# FAL65816_ram.net
KiCad netlist of a schematic drawn in EAGLE
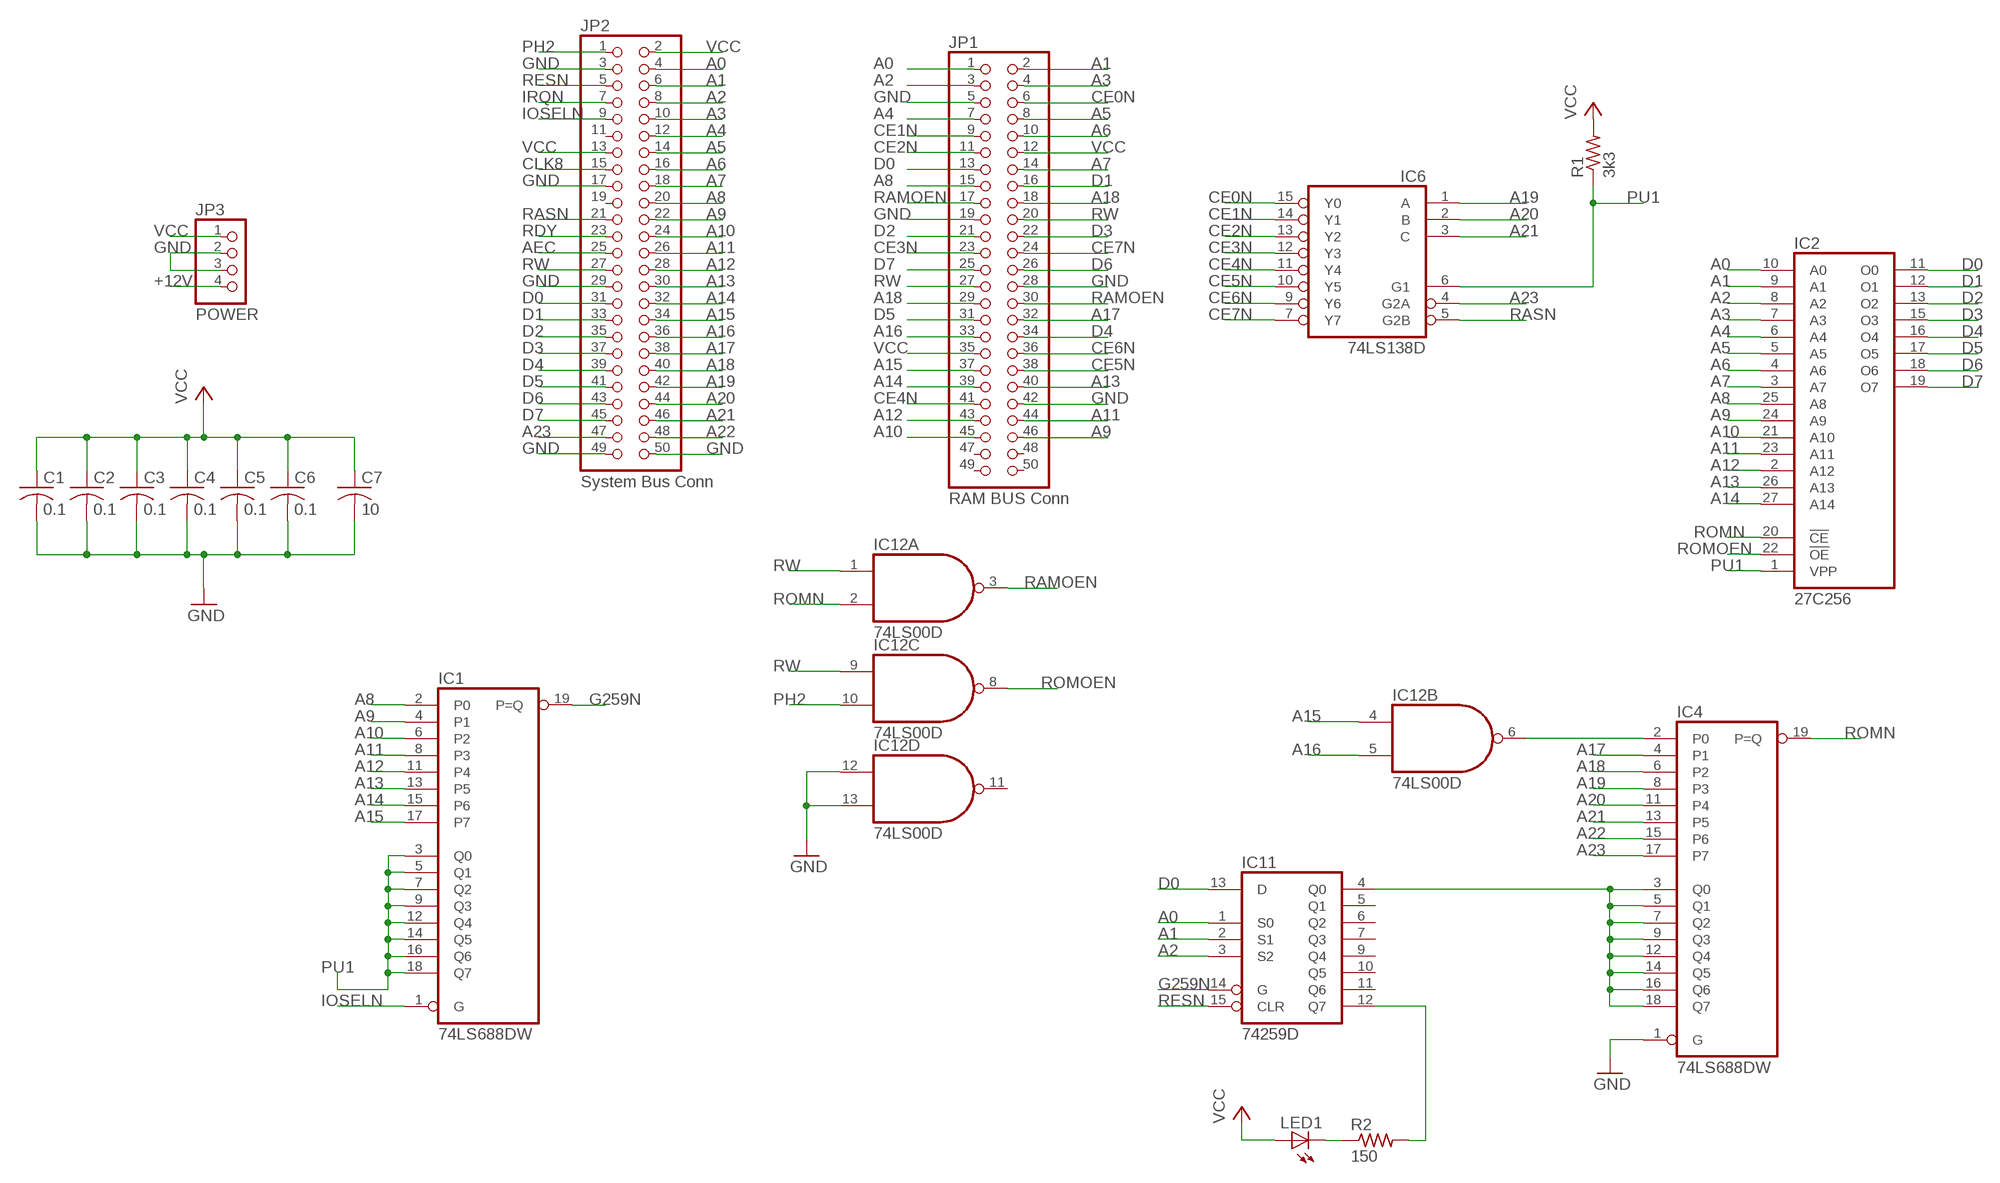
[diagram p0: schematic, sheet 1]

(export (version "E")
  (design (tool "Eeschema 10.0.6"))
  (components
    (comp (ref "C1")
      (value "0.1")
      (footprint "eagle-import:C050-024X044")
      (libsource (lib "eagle-import") (part "C-US050-024X044"))
    )
    (comp (ref "C2")
      (value "0.1")
      (footprint "eagle-import:C050-024X044")
      (libsource (lib "eagle-import") (part "C-US050-024X044"))
    )
    (comp (ref "C3")
      (value "0.1")
      (footprint "eagle-import:C050-024X044")
      (libsource (lib "eagle-import") (part "C-US050-024X044"))
    )
    (comp (ref "C4")
      (value "0.1")
      (footprint "eagle-import:C050-024X044")
      (libsource (lib "eagle-import") (part "C-US050-024X044"))
    )
    (comp (ref "C5")
      (value "0.1")
      (footprint "eagle-import:C050-024X044")
      (libsource (lib "eagle-import") (part "C-US050-024X044"))
    )
    (comp (ref "C6")
      (value "0.1")
      (footprint "eagle-import:C050-024X044")
      (libsource (lib "eagle-import") (part "C-US050-024X044"))
    )
    (comp (ref "C7")
      (value "10")
      (footprint "eagle-import:C050-024X044")
      (libsource (lib "eagle-import") (part "C-US050-024X044"))
    )
    (comp (ref "IC1")
      (value "74LS688DW")
      (footprint "eagle-import:SO20W")
      (libsource (lib "eagle-import") (part "74688DWLS"))
    )
    (comp (ref "IC2")
      (value "27C256")
      (footprint "eagle-import:DIL28")
      (libsource (lib "eagle-import") (part "27256"))
    )
    (comp (ref "IC4")
      (value "74LS688DW")
      (footprint "eagle-import:SO20W")
      (libsource (lib "eagle-import") (part "74688DWLS"))
    )
    (comp (ref "IC6")
      (value "74LS138D")
      (footprint "eagle-import:SO16")
      (libsource (lib "eagle-import") (part "74138DLS"))
    )
    (comp (ref "IC11")
      (value "74259D")
      (footprint "eagle-import:SO16")
      (libsource (lib "eagle-import") (part "74259D"))
    )
    (comp (ref "IC12")
      (value "74LS00D")
      (footprint "eagle-import:SO14")
      (libsource (lib "eagle-import") (part "7400DLS"))
    )
    (comp (ref "JP1")
      (value "RAM BUS Conn")
      (footprint "eagle-import:2X25_90")
      (libsource (lib "eagle-import") (part "PINHD-2X25/90"))
    )
    (comp (ref "JP2")
      (value "System Bus Conn")
      (footprint "eagle-import:2X25_90")
      (libsource (lib "eagle-import") (part "PINHD-2X25/90"))
    )
    (comp (ref "JP3")
      (value "POWER")
      (footprint "eagle-import:1X04_90")
      (libsource (lib "eagle-import") (part "PINHD-1X4/90"))
    )
    (comp (ref "LED1")
      (value "LED5MM")
      (footprint "eagle-import:LED5MM")
      (libsource (lib "eagle-import") (part "LED5MM"))
    )
    (comp (ref "R1")
      (value "3k3")
      (footprint "eagle-import:0204_7")
      (libsource (lib "eagle-import") (part "R-US_0204/7"))
    )
    (comp (ref "R2")
      (value "150")
      (footprint "eagle-import:0204_7")
      (libsource (lib "eagle-import") (part "R-US_0204/7"))
    )
  )
  (nets
    (net (code "1") (name "/+12V") (class "Default")
      (node (ref "JP3") (pin "4") (pinfunction "4_4") (pintype "passive"))
    )
    (net (code "2") (name "/A0") (class "Default")
      (node (ref "IC11") (pin "1") (pinfunction "S0_1") (pintype "input"))
      (node (ref "IC2") (pin "10") (pinfunction "A0_10") (pintype "input"))
      (node (ref "JP1") (pin "1") (pinfunction "1_1") (pintype "passive"))
      (node (ref "JP2") (pin "4") (pinfunction "4_4") (pintype "passive"))
    )
    (net (code "3") (name "/A1") (class "Default")
      (node (ref "IC11") (pin "2") (pinfunction "S1_2") (pintype "input"))
      (node (ref "IC2") (pin "9") (pinfunction "A1_9") (pintype "input"))
      (node (ref "JP1") (pin "2") (pinfunction "2_2") (pintype "passive"))
      (node (ref "JP2") (pin "6") (pinfunction "6_6") (pintype "passive"))
    )
    (net (code "4") (name "/A2") (class "Default")
      (node (ref "IC11") (pin "3") (pinfunction "S2_3") (pintype "input"))
      (node (ref "IC2") (pin "8") (pinfunction "A2_8") (pintype "input"))
      (node (ref "JP1") (pin "3") (pinfunction "3_3") (pintype "passive"))
      (node (ref "JP2") (pin "8") (pinfunction "8_8") (pintype "passive"))
    )
    (net (code "5") (name "/A3") (class "Default")
      (node (ref "IC2") (pin "7") (pinfunction "A3_7") (pintype "input"))
      (node (ref "JP1") (pin "4") (pinfunction "4_4") (pintype "passive"))
      (node (ref "JP2") (pin "10") (pinfunction "10_10") (pintype "passive"))
    )
    (net (code "6") (name "/A4") (class "Default")
      (node (ref "IC2") (pin "6") (pinfunction "A4_6") (pintype "input"))
      (node (ref "JP1") (pin "7") (pinfunction "7_7") (pintype "passive"))
      (node (ref "JP2") (pin "12") (pinfunction "12_12") (pintype "passive"))
    )
    (net (code "7") (name "/A5") (class "Default")
      (node (ref "IC2") (pin "5") (pinfunction "A5_5") (pintype "input"))
      (node (ref "JP1") (pin "8") (pinfunction "8_8") (pintype "passive"))
      (node (ref "JP2") (pin "14") (pinfunction "14_14") (pintype "passive"))
    )
    (net (code "8") (name "/A6") (class "Default")
      (node (ref "IC2") (pin "4") (pinfunction "A6_4") (pintype "input"))
      (node (ref "JP1") (pin "10") (pinfunction "10_10") (pintype "passive"))
      (node (ref "JP2") (pin "16") (pinfunction "16_16") (pintype "passive"))
    )
    (net (code "9") (name "/A7") (class "Default")
      (node (ref "IC2") (pin "3") (pinfunction "A7_3") (pintype "input"))
      (node (ref "JP1") (pin "14") (pinfunction "14_14") (pintype "passive"))
      (node (ref "JP2") (pin "18") (pinfunction "18_18") (pintype "passive"))
    )
    (net (code "10") (name "/A8") (class "Default")
      (node (ref "IC1") (pin "2") (pinfunction "P0_2") (pintype "input"))
      (node (ref "IC2") (pin "25") (pinfunction "A8_25") (pintype "input"))
      (node (ref "JP1") (pin "15") (pinfunction "15_15") (pintype "passive"))
      (node (ref "JP2") (pin "20") (pinfunction "20_20") (pintype "passive"))
    )
    (net (code "11") (name "/A9") (class "Default")
      (node (ref "IC1") (pin "4") (pinfunction "P1_4") (pintype "input"))
      (node (ref "IC2") (pin "24") (pinfunction "A9_24") (pintype "input"))
      (node (ref "JP1") (pin "46") (pinfunction "46_46") (pintype "passive"))
      (node (ref "JP2") (pin "22") (pinfunction "22_22") (pintype "passive"))
    )
    (net (code "12") (name "/A10") (class "Default")
      (node (ref "IC1") (pin "6") (pinfunction "P2_6") (pintype "input"))
      (node (ref "IC2") (pin "21") (pinfunction "A10_21") (pintype "input"))
      (node (ref "JP1") (pin "45") (pinfunction "45_45") (pintype "passive"))
      (node (ref "JP2") (pin "24") (pinfunction "24_24") (pintype "passive"))
    )
    (net (code "13") (name "/A11") (class "Default")
      (node (ref "IC1") (pin "8") (pinfunction "P3_8") (pintype "input"))
      (node (ref "IC2") (pin "23") (pinfunction "A11_23") (pintype "input"))
      (node (ref "JP1") (pin "44") (pinfunction "44_44") (pintype "passive"))
      (node (ref "JP2") (pin "26") (pinfunction "26_26") (pintype "passive"))
    )
    (net (code "14") (name "/A12") (class "Default")
      (node (ref "IC1") (pin "11") (pinfunction "P4_11") (pintype "input"))
      (node (ref "IC2") (pin "2") (pinfunction "A12_2") (pintype "input"))
      (node (ref "JP1") (pin "43") (pinfunction "43_43") (pintype "passive"))
      (node (ref "JP2") (pin "28") (pinfunction "28_28") (pintype "passive"))
    )
    (net (code "15") (name "/A13") (class "Default")
      (node (ref "IC1") (pin "13") (pinfunction "P5_13") (pintype "input"))
      (node (ref "IC2") (pin "26") (pinfunction "A13_26") (pintype "input"))
      (node (ref "JP1") (pin "40") (pinfunction "40_40") (pintype "passive"))
      (node (ref "JP2") (pin "30") (pinfunction "30_30") (pintype "passive"))
    )
    (net (code "16") (name "/A14") (class "Default")
      (node (ref "IC1") (pin "15") (pinfunction "P6_15") (pintype "input"))
      (node (ref "IC2") (pin "27") (pinfunction "A14_27") (pintype "input"))
      (node (ref "JP1") (pin "39") (pinfunction "39_39") (pintype "passive"))
      (node (ref "JP2") (pin "32") (pinfunction "32_32") (pintype "passive"))
    )
    (net (code "17") (name "/A15") (class "Default")
      (node (ref "IC1") (pin "17") (pinfunction "P7_17") (pintype "input"))
      (node (ref "IC12") (pin "4") (pinfunction "I0_4") (pintype "input"))
      (node (ref "JP1") (pin "37") (pinfunction "37_37") (pintype "passive"))
      (node (ref "JP2") (pin "34") (pinfunction "34_34") (pintype "passive"))
    )
    (net (code "18") (name "/A16") (class "Default")
      (node (ref "IC12") (pin "5") (pinfunction "I1_5") (pintype "input"))
      (node (ref "JP1") (pin "33") (pinfunction "33_33") (pintype "passive"))
      (node (ref "JP2") (pin "36") (pinfunction "36_36") (pintype "passive"))
    )
    (net (code "19") (name "/A17") (class "Default")
      (node (ref "IC4") (pin "4") (pinfunction "P1_4") (pintype "input"))
      (node (ref "JP1") (pin "32") (pinfunction "32_32") (pintype "passive"))
      (node (ref "JP2") (pin "38") (pinfunction "38_38") (pintype "passive"))
    )
    (net (code "20") (name "/A18") (class "Default")
      (node (ref "IC4") (pin "6") (pinfunction "P2_6") (pintype "input"))
      (node (ref "JP1") (pin "18") (pinfunction "18_18") (pintype "passive"))
      (node (ref "JP1") (pin "29") (pinfunction "29_29") (pintype "passive"))
      (node (ref "JP2") (pin "40") (pinfunction "40_40") (pintype "passive"))
    )
    (net (code "21") (name "/A19") (class "Default")
      (node (ref "IC4") (pin "8") (pinfunction "P3_8") (pintype "input"))
      (node (ref "IC6") (pin "1") (pinfunction "A_1") (pintype "input"))
      (node (ref "JP2") (pin "42") (pinfunction "42_42") (pintype "passive"))
    )
    (net (code "22") (name "/A20") (class "Default")
      (node (ref "IC4") (pin "11") (pinfunction "P4_11") (pintype "input"))
      (node (ref "IC6") (pin "2") (pinfunction "B_2") (pintype "input"))
      (node (ref "JP2") (pin "44") (pinfunction "44_44") (pintype "passive"))
    )
    (net (code "23") (name "/A21") (class "Default")
      (node (ref "IC4") (pin "13") (pinfunction "P5_13") (pintype "input"))
      (node (ref "IC6") (pin "3") (pinfunction "C_3") (pintype "input"))
      (node (ref "JP2") (pin "46") (pinfunction "46_46") (pintype "passive"))
    )
    (net (code "24") (name "/A22") (class "Default")
      (node (ref "IC4") (pin "15") (pinfunction "P6_15") (pintype "input"))
      (node (ref "JP2") (pin "48") (pinfunction "48_48") (pintype "passive"))
    )
    (net (code "25") (name "/A23") (class "Default")
      (node (ref "IC4") (pin "17") (pinfunction "P7_17") (pintype "input"))
      (node (ref "IC6") (pin "4") (pinfunction "G2A_4") (pintype "input"))
      (node (ref "JP2") (pin "47") (pinfunction "47_47") (pintype "passive"))
    )
    (net (code "26") (name "/AEC") (class "Default")
      (node (ref "JP2") (pin "25") (pinfunction "25_25") (pintype "passive"))
    )
    (net (code "27") (name "/CE0N") (class "Default")
      (node (ref "IC6") (pin "15") (pinfunction "Y0_15") (pintype "output"))
      (node (ref "JP1") (pin "6") (pinfunction "6_6") (pintype "passive"))
    )
    (net (code "28") (name "/CE1N") (class "Default")
      (node (ref "IC6") (pin "14") (pinfunction "Y1_14") (pintype "output"))
      (node (ref "JP1") (pin "9") (pinfunction "9_9") (pintype "passive"))
    )
    (net (code "29") (name "/CE2N") (class "Default")
      (node (ref "IC6") (pin "13") (pinfunction "Y2_13") (pintype "output"))
      (node (ref "JP1") (pin "11") (pinfunction "11_11") (pintype "passive"))
    )
    (net (code "30") (name "/CE3N") (class "Default")
      (node (ref "IC6") (pin "12") (pinfunction "Y3_12") (pintype "output"))
      (node (ref "JP1") (pin "23") (pinfunction "23_23") (pintype "passive"))
    )
    (net (code "31") (name "/CE4N") (class "Default")
      (node (ref "IC6") (pin "11") (pinfunction "Y4_11") (pintype "output"))
      (node (ref "JP1") (pin "41") (pinfunction "41_41") (pintype "passive"))
    )
    (net (code "32") (name "/CE5N") (class "Default")
      (node (ref "IC6") (pin "10") (pinfunction "Y5_10") (pintype "output"))
      (node (ref "JP1") (pin "38") (pinfunction "38_38") (pintype "passive"))
    )
    (net (code "33") (name "/CE6N") (class "Default")
      (node (ref "IC6") (pin "9") (pinfunction "Y6_9") (pintype "output"))
      (node (ref "JP1") (pin "36") (pinfunction "36_36") (pintype "passive"))
    )
    (net (code "34") (name "/CE7N") (class "Default")
      (node (ref "IC6") (pin "7") (pinfunction "Y7_7") (pintype "output"))
      (node (ref "JP1") (pin "24") (pinfunction "24_24") (pintype "passive"))
    )
    (net (code "35") (name "/CLK8") (class "Default")
      (node (ref "JP2") (pin "15") (pinfunction "15_15") (pintype "passive"))
    )
    (net (code "36") (name "/D0") (class "Default")
      (node (ref "IC11") (pin "13") (pinfunction "D_13") (pintype "input"))
      (node (ref "IC2") (pin "11") (pinfunction "O0_11") (pintype "tri_state"))
      (node (ref "JP1") (pin "13") (pinfunction "13_13") (pintype "passive"))
      (node (ref "JP2") (pin "31") (pinfunction "31_31") (pintype "passive"))
    )
    (net (code "37") (name "/D1") (class "Default")
      (node (ref "IC2") (pin "12") (pinfunction "O1_12") (pintype "tri_state"))
      (node (ref "JP1") (pin "16") (pinfunction "16_16") (pintype "passive"))
      (node (ref "JP2") (pin "33") (pinfunction "33_33") (pintype "passive"))
    )
    (net (code "38") (name "/D2") (class "Default")
      (node (ref "IC2") (pin "13") (pinfunction "O2_13") (pintype "tri_state"))
      (node (ref "JP1") (pin "21") (pinfunction "21_21") (pintype "passive"))
      (node (ref "JP2") (pin "35") (pinfunction "35_35") (pintype "passive"))
    )
    (net (code "39") (name "/D3") (class "Default")
      (node (ref "IC2") (pin "15") (pinfunction "O3_15") (pintype "tri_state"))
      (node (ref "JP1") (pin "22") (pinfunction "22_22") (pintype "passive"))
      (node (ref "JP2") (pin "37") (pinfunction "37_37") (pintype "passive"))
    )
    (net (code "40") (name "/D4") (class "Default")
      (node (ref "IC2") (pin "16") (pinfunction "O4_16") (pintype "tri_state"))
      (node (ref "JP1") (pin "34") (pinfunction "34_34") (pintype "passive"))
      (node (ref "JP2") (pin "39") (pinfunction "39_39") (pintype "passive"))
    )
    (net (code "41") (name "/D5") (class "Default")
      (node (ref "IC2") (pin "17") (pinfunction "O5_17") (pintype "tri_state"))
      (node (ref "JP1") (pin "31") (pinfunction "31_31") (pintype "passive"))
      (node (ref "JP2") (pin "41") (pinfunction "41_41") (pintype "passive"))
    )
    (net (code "42") (name "/D6") (class "Default")
      (node (ref "IC2") (pin "18") (pinfunction "O6_18") (pintype "tri_state"))
      (node (ref "JP1") (pin "26") (pinfunction "26_26") (pintype "passive"))
      (node (ref "JP2") (pin "43") (pinfunction "43_43") (pintype "passive"))
    )
    (net (code "43") (name "/D7") (class "Default")
      (node (ref "IC2") (pin "19") (pinfunction "O7_19") (pintype "tri_state"))
      (node (ref "JP1") (pin "25") (pinfunction "25_25") (pintype "passive"))
      (node (ref "JP2") (pin "45") (pinfunction "45_45") (pintype "passive"))
    )
    (net (code "44") (name "/G259N") (class "Default")
      (node (ref "IC1") (pin "19") (pinfunction "P=Q_19") (pintype "output"))
      (node (ref "IC11") (pin "14") (pinfunction "G_14") (pintype "input"))
    )
    (net (code "45") (name "/IOSELN") (class "Default")
      (node (ref "IC1") (pin "1") (pinfunction "G_1") (pintype "input"))
      (node (ref "JP2") (pin "9") (pinfunction "9_9") (pintype "passive"))
    )
    (net (code "46") (name "/IRQN") (class "Default")
      (node (ref "JP2") (pin "7") (pinfunction "7_7") (pintype "passive"))
    )
    (net (code "47") (name "/PH2") (class "Default")
      (node (ref "IC12") (pin "10") (pinfunction "I1_10") (pintype "input"))
      (node (ref "JP2") (pin "1") (pinfunction "1_1") (pintype "passive"))
    )
    (net (code "48") (name "/PU1") (class "Default")
      (node (ref "IC1") (pin "12") (pinfunction "Q4_12") (pintype "input"))
      (node (ref "IC1") (pin "14") (pinfunction "Q5_14") (pintype "input"))
      (node (ref "IC1") (pin "16") (pinfunction "Q6_16") (pintype "input"))
      (node (ref "IC1") (pin "18") (pinfunction "Q7_18") (pintype "input"))
      (node (ref "IC1") (pin "3") (pinfunction "Q0_3") (pintype "input"))
      (node (ref "IC1") (pin "5") (pinfunction "Q1_5") (pintype "input"))
      (node (ref "IC1") (pin "7") (pinfunction "Q2_7") (pintype "input"))
      (node (ref "IC1") (pin "9") (pinfunction "Q3_9") (pintype "input"))
      (node (ref "IC2") (pin "1") (pinfunction "VPP_1") (pintype "input"))
      (node (ref "IC6") (pin "6") (pinfunction "G1_6") (pintype "input"))
      (node (ref "R1") (pin "1") (pinfunction "1_1") (pintype "passive"))
    )
    (net (code "49") (name "/RAMOEN") (class "Default")
      (node (ref "IC12") (pin "3") (pinfunction "O_3") (pintype "output"))
      (node (ref "JP1") (pin "17") (pinfunction "17_17") (pintype "passive"))
      (node (ref "JP1") (pin "30") (pinfunction "30_30") (pintype "passive"))
    )
    (net (code "50") (name "/RASN") (class "Default")
      (node (ref "IC6") (pin "5") (pinfunction "G2B_5") (pintype "input"))
      (node (ref "JP2") (pin "21") (pinfunction "21_21") (pintype "passive"))
    )
    (net (code "51") (name "/RDY") (class "Default")
      (node (ref "JP2") (pin "23") (pinfunction "23_23") (pintype "passive"))
    )
    (net (code "52") (name "/RESN") (class "Default")
      (node (ref "IC11") (pin "15") (pinfunction "CLR_15") (pintype "input"))
      (node (ref "JP2") (pin "5") (pinfunction "5_5") (pintype "passive"))
    )
    (net (code "53") (name "/ROMN") (class "Default")
      (node (ref "IC12") (pin "2") (pinfunction "I1_2") (pintype "input"))
      (node (ref "IC2") (pin "20") (pinfunction "~{CE}_20") (pintype "input"))
      (node (ref "IC4") (pin "19") (pinfunction "P=Q_19") (pintype "output"))
    )
    (net (code "54") (name "/ROMOEN") (class "Default")
      (node (ref "IC12") (pin "8") (pinfunction "O_8") (pintype "output"))
      (node (ref "IC2") (pin "22") (pinfunction "~{OE}_22") (pintype "input"))
    )
    (net (code "55") (name "/RW") (class "Default")
      (node (ref "IC12") (pin "1") (pinfunction "I0_1") (pintype "input"))
      (node (ref "IC12") (pin "9") (pinfunction "I0_9") (pintype "input"))
      (node (ref "JP1") (pin "20") (pinfunction "20_20") (pintype "passive"))
      (node (ref "JP1") (pin "27") (pinfunction "27_27") (pintype "passive"))
      (node (ref "JP2") (pin "27") (pinfunction "27_27") (pintype "passive"))
    )
    (net (code "56") (name "GND") (class "Default")
      (node (ref "C1") (pin "2") (pinfunction "2_2") (pintype "passive"))
      (node (ref "C2") (pin "2") (pinfunction "2_2") (pintype "passive"))
      (node (ref "C3") (pin "2") (pinfunction "2_2") (pintype "passive"))
      (node (ref "C4") (pin "2") (pinfunction "2_2") (pintype "passive"))
      (node (ref "C5") (pin "2") (pinfunction "2_2") (pintype "passive"))
      (node (ref "C6") (pin "2") (pinfunction "2_2") (pintype "passive"))
      (node (ref "C7") (pin "2") (pinfunction "2_2") (pintype "passive"))
      (node (ref "IC12") (pin "12") (pinfunction "I0_12") (pintype "input"))
      (node (ref "IC12") (pin "13") (pinfunction "I1_13") (pintype "input"))
      (node (ref "IC4") (pin "1") (pinfunction "G_1") (pintype "input"))
      (node (ref "JP1") (pin "19") (pinfunction "19_19") (pintype "passive"))
      (node (ref "JP1") (pin "28") (pinfunction "28_28") (pintype "passive"))
      (node (ref "JP1") (pin "42") (pinfunction "42_42") (pintype "passive"))
      (node (ref "JP1") (pin "5") (pinfunction "5_5") (pintype "passive"))
      (node (ref "JP2") (pin "17") (pinfunction "17_17") (pintype "passive"))
      (node (ref "JP2") (pin "29") (pinfunction "29_29") (pintype "passive"))
      (node (ref "JP2") (pin "3") (pinfunction "3_3") (pintype "passive"))
      (node (ref "JP2") (pin "49") (pinfunction "49_49") (pintype "passive"))
      (node (ref "JP2") (pin "50") (pinfunction "50_50") (pintype "passive"))
      (node (ref "JP3") (pin "2") (pinfunction "2_2") (pintype "passive"))
      (node (ref "JP3") (pin "3") (pinfunction "3_3") (pintype "passive"))
    )
    (net (code "57") (name "Net-(IC11A-Q0)") (class "Default")
      (node (ref "IC11") (pin "4") (pinfunction "Q0_4") (pintype "output"))
      (node (ref "IC4") (pin "12") (pinfunction "Q4_12") (pintype "input"))
      (node (ref "IC4") (pin "14") (pinfunction "Q5_14") (pintype "input"))
      (node (ref "IC4") (pin "16") (pinfunction "Q6_16") (pintype "input"))
      (node (ref "IC4") (pin "18") (pinfunction "Q7_18") (pintype "input"))
      (node (ref "IC4") (pin "3") (pinfunction "Q0_3") (pintype "input"))
      (node (ref "IC4") (pin "5") (pinfunction "Q1_5") (pintype "input"))
      (node (ref "IC4") (pin "7") (pinfunction "Q2_7") (pintype "input"))
      (node (ref "IC4") (pin "9") (pinfunction "Q3_9") (pintype "input"))
    )
    (net (code "58") (name "Net-(IC11A-Q7)") (class "Default")
      (node (ref "IC11") (pin "12") (pinfunction "Q7_12") (pintype "output"))
      (node (ref "R2") (pin "2") (pinfunction "2_2") (pintype "passive"))
    )
    (net (code "59") (name "Net-(IC12B-O)") (class "Default")
      (node (ref "IC12") (pin "6") (pinfunction "O_6") (pintype "output"))
      (node (ref "IC4") (pin "2") (pinfunction "P0_2") (pintype "input"))
    )
    (net (code "60") (name "Net-(LED1-C)") (class "Default")
      (node (ref "LED1") (pin "K") (pinfunction "C_K") (pintype "passive"))
      (node (ref "R2") (pin "1") (pinfunction "1_1") (pintype "passive"))
    )
    (net (code "61") (name "VCC") (class "Default")
      (node (ref "C1") (pin "1") (pinfunction "1_1") (pintype "passive"))
      (node (ref "C2") (pin "1") (pinfunction "1_1") (pintype "passive"))
      (node (ref "C3") (pin "1") (pinfunction "1_1") (pintype "passive"))
      (node (ref "C4") (pin "1") (pinfunction "1_1") (pintype "passive"))
      (node (ref "C5") (pin "1") (pinfunction "1_1") (pintype "passive"))
      (node (ref "C6") (pin "1") (pinfunction "1_1") (pintype "passive"))
      (node (ref "C7") (pin "1") (pinfunction "1_1") (pintype "passive"))
      (node (ref "JP1") (pin "12") (pinfunction "12_12") (pintype "passive"))
      (node (ref "JP1") (pin "35") (pinfunction "35_35") (pintype "passive"))
      (node (ref "JP2") (pin "13") (pinfunction "13_13") (pintype "passive"))
      (node (ref "JP2") (pin "2") (pinfunction "2_2") (pintype "passive"))
      (node (ref "JP3") (pin "1") (pinfunction "1_1") (pintype "passive"))
      (node (ref "LED1") (pin "A") (pinfunction "A_A") (pintype "passive"))
      (node (ref "R1") (pin "2") (pinfunction "2_2") (pintype "passive"))
    )
    (net (code "62") (name "unconnected-(IC11A-Q1-Pad5)") (class "Default")
      (node (ref "IC11") (pin "5") (pinfunction "Q1_5") (pintype "output"))
    )
    (net (code "63") (name "unconnected-(IC11A-Q2-Pad6)") (class "Default")
      (node (ref "IC11") (pin "6") (pinfunction "Q2_6") (pintype "output"))
    )
    (net (code "64") (name "unconnected-(IC11A-Q3-Pad7)") (class "Default")
      (node (ref "IC11") (pin "7") (pinfunction "Q3_7") (pintype "output"))
    )
    (net (code "65") (name "unconnected-(IC11A-Q4-Pad9)") (class "Default")
      (node (ref "IC11") (pin "9") (pinfunction "Q4_9") (pintype "output"))
    )
    (net (code "66") (name "unconnected-(IC11A-Q5-Pad10)") (class "Default")
      (node (ref "IC11") (pin "10") (pinfunction "Q5_10") (pintype "output"))
    )
    (net (code "67") (name "unconnected-(IC11A-Q6-Pad11)") (class "Default")
      (node (ref "IC11") (pin "11") (pinfunction "Q6_11") (pintype "output"))
    )
    (net (code "68") (name "unconnected-(IC12D-O-Pad11)") (class "Default")
      (node (ref "IC12") (pin "11") (pinfunction "O_11") (pintype "output"))
    )
    (net (code "69") (name "unconnected-(JP1-Pad47)") (class "Default")
      (node (ref "JP1") (pin "47") (pinfunction "47_47") (pintype "passive"))
    )
    (net (code "70") (name "unconnected-(JP1-Pad48)") (class "Default")
      (node (ref "JP1") (pin "48") (pinfunction "48_48") (pintype "passive"))
    )
    (net (code "71") (name "unconnected-(JP1-Pad49)") (class "Default")
      (node (ref "JP1") (pin "49") (pinfunction "49_49") (pintype "passive"))
    )
    (net (code "72") (name "unconnected-(JP1-Pad50)") (class "Default")
      (node (ref "JP1") (pin "50") (pinfunction "50_50") (pintype "passive"))
    )
    (net (code "73") (name "unconnected-(JP2-Pad11)") (class "Default")
      (node (ref "JP2") (pin "11") (pinfunction "11_11") (pintype "passive"))
    )
    (net (code "74") (name "unconnected-(JP2-Pad19)") (class "Default")
      (node (ref "JP2") (pin "19") (pinfunction "19_19") (pintype "passive"))
    )
  )
)
